# Sheet1.net
KiCad netlist of a schematic drawn in Altium Designer
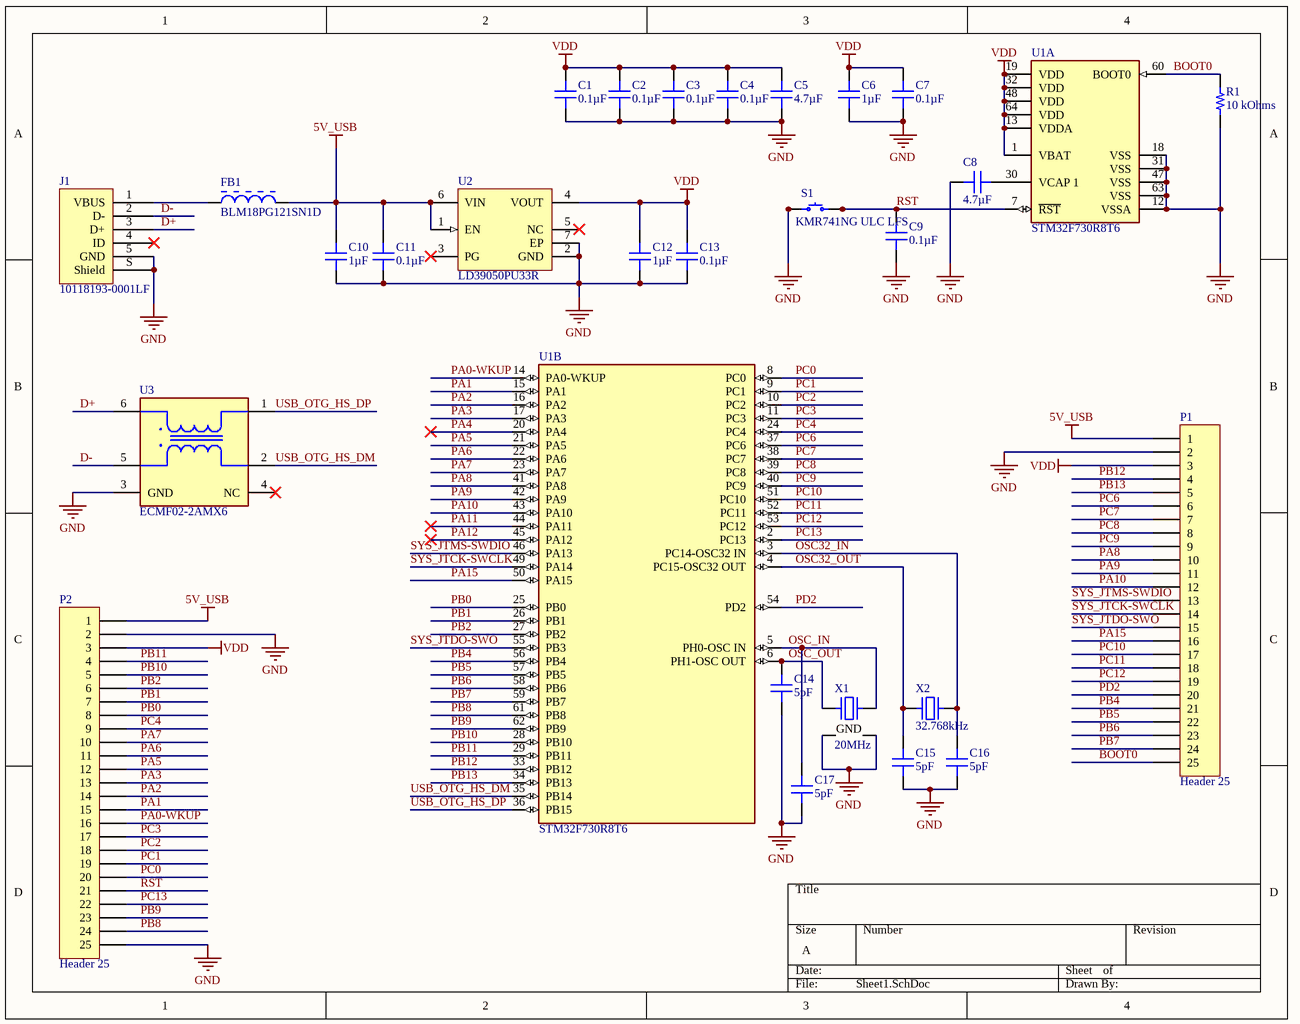
[diagram p0: Sheet1.SchDoc]

(export (version "E")
  (design (tool "Eeschema 10.0.6"))
  (components
    (comp (ref "C1")
      (value "0.1µF")
      (footprint "CAP 0603_1608")
      (description "CAP CER 0.1UF 25V X7R 0603")
      (fields (field (name "PART NUMBER") "06033C104KAZ2A") (field (name "MANUFACTURER") "AVX Corporation"))
      (libsource (lib "Celestial Altium Library - altium_library") (part "Capacitor"))
    )
    (comp (ref "C2")
      (value "0.1µF")
      (footprint "CAP 0603_1608")
      (description "CAP CER 0.1UF 25V X7R 0603")
      (fields (field (name "PART NUMBER") "06033C104KAZ2A") (field (name "MANUFACTURER") "AVX Corporation"))
      (libsource (lib "Celestial Altium Library - altium_library") (part "Capacitor"))
    )
    (comp (ref "C3")
      (value "0.1µF")
      (footprint "CAP 0603_1608")
      (description "CAP CER 0.1UF 25V X7R 0603")
      (fields (field (name "PART NUMBER") "06033C104KAZ2A") (field (name "MANUFACTURER") "AVX Corporation"))
      (libsource (lib "Celestial Altium Library - altium_library") (part "Capacitor"))
    )
    (comp (ref "C4")
      (value "0.1µF")
      (footprint "CAP 0603_1608")
      (description "CAP CER 0.1UF 25V X7R 0603")
      (fields (field (name "PART NUMBER") "06033C104KAZ2A") (field (name "MANUFACTURER") "AVX Corporation"))
      (libsource (lib "Celestial Altium Library - altium_library") (part "Capacitor"))
    )
    (comp (ref "C5")
      (value "4.7µF")
      (footprint "CAP 0603_1608")
      (description "CAP CER 4.7UF 16V X7S 0603")
      (fields
        (field (name "PART NUMBER") "GRM188C71C475KE21D")
        (field (name "MANUFACTURER") "Murata Electronics")
      )
      (libsource (lib "Celestial Altium Library - altium_library") (part "Capacitor"))
    )
    (comp (ref "C6")
      (value "1µF")
      (footprint "CAP 0603_1608")
      (description "CAP CER 1UF 25V X7R 0603")
      (fields (field (name "PART NUMBER") "06033C105KAT4A") (field (name "MANUFACTURER") "AVX Corporation"))
      (libsource (lib "Celestial Altium Library - altium_library") (part "Capacitor"))
    )
    (comp (ref "C7")
      (value "0.1µF")
      (footprint "CAP 0603_1608")
      (description "CAP CER 0.1UF 25V X7R 0603")
      (fields (field (name "PART NUMBER") "06033C104KAZ2A") (field (name "MANUFACTURER") "AVX Corporation"))
      (libsource (lib "Celestial Altium Library - altium_library") (part "Capacitor"))
    )
    (comp (ref "C8")
      (value "4.7µF")
      (footprint "CAP 0603_1608")
      (description "CAP CER 4.7UF 16V X7S 0603")
      (fields
        (field (name "PART NUMBER") "GRM188C71C475KE21D")
        (field (name "MANUFACTURER") "Murata Electronics")
      )
      (libsource (lib "Celestial Altium Library - altium_library") (part "Capacitor"))
    )
    (comp (ref "C9")
      (value "0.1µF")
      (footprint "CAP 0603_1608")
      (description "CAP CER 0.1UF 25V X7R 0603")
      (fields (field (name "PART NUMBER") "06033C104KAZ2A") (field (name "MANUFACTURER") "AVX Corporation"))
      (libsource (lib "Celestial Altium Library - altium_library") (part "Capacitor"))
    )
    (comp (ref "C10")
      (value "1µF")
      (footprint "CAP 0603_1608")
      (description "CAP CER 1UF 25V X7R 0603")
      (fields (field (name "PART NUMBER") "06033C105KAT4A") (field (name "MANUFACTURER") "AVX Corporation"))
      (libsource (lib "Celestial Altium Library - altium_library") (part "Capacitor"))
    )
    (comp (ref "C11")
      (value "0.1µF")
      (footprint "CAP 0603_1608")
      (description "CAP CER 0.1UF 25V X7R 0603")
      (fields (field (name "PART NUMBER") "06033C104KAZ2A") (field (name "MANUFACTURER") "AVX Corporation"))
      (libsource (lib "Celestial Altium Library - altium_library") (part "Capacitor"))
    )
    (comp (ref "C12")
      (value "1µF")
      (footprint "CAP 0603_1608")
      (description "CAP CER 1UF 25V X7R 0603")
      (fields (field (name "PART NUMBER") "06033C105KAT4A") (field (name "MANUFACTURER") "AVX Corporation"))
      (libsource (lib "Celestial Altium Library - altium_library") (part "Capacitor"))
    )
    (comp (ref "C13")
      (value "0.1µF")
      (footprint "CAP 0603_1608")
      (description "CAP CER 0.1UF 25V X7R 0603")
      (fields (field (name "PART NUMBER") "06033C104KAZ2A") (field (name "MANUFACTURER") "AVX Corporation"))
      (libsource (lib "Celestial Altium Library - altium_library") (part "Capacitor"))
    )
    (comp (ref "C14")
      (value "5pF")
      (footprint "CAP 0603_1608")
      (description "CAP CER 5PF 50V NP0 0603")
      (fields (field (name "PART NUMBER") "CBR06C509A5GAC") (field (name "MANUFACTURER") "KEMET"))
      (libsource (lib "Celestial Altium Library - altium_library") (part "Capacitor"))
    )
    (comp (ref "C15")
      (value "5pF")
      (footprint "CAP 0603_1608")
      (description "CAP CER 5PF 50V NP0 0603")
      (fields (field (name "PART NUMBER") "CBR06C509A5GAC") (field (name "MANUFACTURER") "KEMET"))
      (libsource (lib "Celestial Altium Library - altium_library") (part "Capacitor"))
    )
    (comp (ref "C16")
      (value "5pF")
      (footprint "CAP 0603_1608")
      (description "CAP CER 5PF 50V NP0 0603")
      (fields (field (name "PART NUMBER") "CBR06C509A5GAC") (field (name "MANUFACTURER") "KEMET"))
      (libsource (lib "Celestial Altium Library - altium_library") (part "Capacitor"))
    )
    (comp (ref "C17")
      (value "5pF")
      (footprint "CAP 0603_1608")
      (description "CAP CER 5PF 50V NP0 0603")
      (fields (field (name "PART NUMBER") "CBR06C509A5GAC") (field (name "MANUFACTURER") "KEMET"))
      (libsource (lib "Celestial Altium Library - altium_library") (part "Capacitor"))
    )
    (comp (ref "FB1")
      (value "BLM18PG121SN1D")
      (footprint "MURA-BLM18PG_KG-B25-CHIP-2_V1")
      (fields (field (name "MANUFACTURER") "Murata"))
      (libsource (lib "Altium Content Vault") (part "MURA-FB-2"))
    )
    (comp (ref "J1")
      (value "10118193-0001LF")
      (footprint "FCI USB 10118193-0001LF")
      (description "CONN RCPT USB2.0 MICRO B SMD R/A")
      (fields (field (name "MANUFACTURER") "Amphenol ICC (FCI)"))
      (libsource (lib "Celestial Altium Library - altium_library") (part "USB 2.0 Type B Micro"))
    )
    (comp (ref "P1")
      (value "Header 25")
      (footprint "HDR1X25")
      (description "Header, 25-Pin")
      (fields (field (name "PUBLISHER") "Altium Limited"))
      (libsource (lib "") (part "Header 25_1"))
    )
    (comp (ref "P2")
      (value "Header 25")
      (footprint "HDR1X25")
      (description "Header, 25-Pin")
      (fields (field (name "PUBLISHER") "Altium Limited"))
      (libsource (lib "Miscellaneous Connectors") (part "Header 25"))
    )
    (comp (ref "R1")
      (value "10 kOhms")
      (footprint "RES 0603_1608")
      (description "RES SMD 10K OHM 1% 1/4W 0603")
      (fields
        (field (name "PART NUMBER") "ERJ-PA3F1002V")
        (field (name "MANUFACTURER") "Panasonic Electronic Components")
      )
      (libsource (lib "Celestial Altium Library - altium_library") (part "Resistor"))
    )
    (comp (ref "S1")
      (value "KMR741NG ULC LFS")
      (footprint "C&K KMR7")
      (description "SWITCH TACTILE SPST-NO 50MA 32V")
      (fields (field (name "MANUFACTURER") "C&K"))
      (libsource (lib "Celestial Altium Library - altium_library") (part "SPST-NO 4 PIN"))
    )
    (comp (ref "U1")
      (value "STM32F730R8T6")
      (footprint "FP-LQFP64-5W-IPC_C")
      (fields (field (name "MANUFACTURER") "STMicroelectronics"))
      (libsource (lib "Schlib1") (part "STM32F730R8T6"))
    )
    (comp (ref "U2")
      (value "LD39050PU33R")
      (footprint "DFN6D_L")
      (description "500 mA Low Quiescent Current Low Noise Voltage Regulator, 3.3V, 6-Pin VDFDPN, Tape and Reel")
      (libsource (lib "Altium Content Vault") (part "PM-REG-LD39050-SQ7"))
    )
    (comp (ref "U3")
      (value "ECMF02-2AMX6")
      (footprint "FP-QFN-6L-MFG")
      (description "CMC 200MA 2LN SMD ESD")
      (fields
        (field (name "MANUFACTURER") "STMicroelectronics")
        (field (name "OCTOPART") "https://octopart.com/ecmf02-2amx6-stmicroelectronics-44353078")
      )
      (libsource (lib "Altium Content Vault") (part "8feffc7f24acfb857157da90e949b57"))
    )
    (comp (ref "X1")
      (value "20MHz")
      (footprint "NDK NX3225SA")
      (description "CRYSTAL 20.0000MHZ 8PF SMD")
      (fields
        (field (name "PART NUMBER") "NX3225SA-20.000M-STD-CSR-1")
        (field (name "MANUFACTURER") "NDK America, Inc.")
      )
      (libsource (lib "Celestial Altium Library - altium_library") (part "NDK Crystal NX3225SA"))
    )
    (comp (ref "X2")
      (value "32.768kHz")
      (footprint "ABRACON ABS06")
      (description "IOT 32.786KHZ XTAL")
      (fields
        (field (name "PART NUMBER") "ABS06-127-32.768KHZ-T")
        (field (name "MANUFACTURER") "Abracon LLC")
      )
      (libsource (lib "Celestial Altium Library - altium_library") (part "Abracon Crystal ABS06"))
    )
  )
  (nets
    (net (code "1") (name "/BOOT0") (class "Default")
      (node (ref "P1") (pin "25") (pinfunction "25_25") (pintype "passive"))
      (node (ref "R1") (pin "2") (pinfunction "2_2") (pintype "passive"))
      (node (ref "U1") (pin "60") (pinfunction "BOOT0_60") (pintype "input"))
    )
    (net (code "2") (name "/D+") (class "Default")
      (node (ref "J1") (pin "3") (pinfunction "D+_3") (pintype "passive"))
      (node (ref "U3") (pin "6") (pinfunction "D+_6") (pintype "passive"))
    )
    (net (code "3") (name "/D-") (class "Default")
      (node (ref "J1") (pin "2") (pinfunction "D-_2") (pintype "passive"))
      (node (ref "U3") (pin "5") (pinfunction "D-_5") (pintype "passive"))
    )
    (net (code "4") (name "/OSC32_IN") (class "Default")
      (node (ref "C16") (pin "2") (pinfunction "2_2") (pintype "passive"))
      (node (ref "U1") (pin "3") (pinfunction "PC14-OSC32_IN_3") (pintype "bidirectional"))
      (node (ref "X2") (pin "2") (pinfunction "2_2") (pintype "passive"))
    )
    (net (code "5") (name "/OSC32_OUT") (class "Default")
      (node (ref "C15") (pin "2") (pinfunction "2_2") (pintype "passive"))
      (node (ref "U1") (pin "4") (pinfunction "PC15-OSC32_OUT_4") (pintype "bidirectional"))
      (node (ref "X2") (pin "1") (pinfunction "1_1") (pintype "passive"))
    )
    (net (code "6") (name "/OSC_IN") (class "Default")
      (node (ref "C17") (pin "2") (pinfunction "2_2") (pintype "passive"))
      (node (ref "U1") (pin "5") (pinfunction "PH0-OSC_IN_5") (pintype "bidirectional"))
      (node (ref "X1") (pin "3") (pinfunction "3_3") (pintype "passive"))
    )
    (net (code "7") (name "/OSC_OUT") (class "Default")
      (node (ref "C14") (pin "2") (pinfunction "2_2") (pintype "passive"))
      (node (ref "U1") (pin "6") (pinfunction "PH1-OSC_OUT_6") (pintype "bidirectional"))
      (node (ref "X1") (pin "1") (pinfunction "1_1") (pintype "passive"))
    )
    (net (code "8") (name "/PA0-WKUP") (class "Default")
      (node (ref "P2") (pin "16") (pinfunction "16_16") (pintype "passive"))
      (node (ref "U1") (pin "14") (pinfunction "PA0-WKUP_14") (pintype "bidirectional"))
    )
    (net (code "9") (name "/PA1") (class "Default")
      (node (ref "P2") (pin "15") (pinfunction "15_15") (pintype "passive"))
      (node (ref "U1") (pin "15") (pinfunction "PA1_15") (pintype "bidirectional"))
    )
    (net (code "10") (name "/PA2") (class "Default")
      (node (ref "P2") (pin "14") (pinfunction "14_14") (pintype "passive"))
      (node (ref "U1") (pin "16") (pinfunction "PA2_16") (pintype "bidirectional"))
    )
    (net (code "11") (name "/PA3") (class "Default")
      (node (ref "P2") (pin "13") (pinfunction "13_13") (pintype "passive"))
      (node (ref "U1") (pin "17") (pinfunction "PA3_17") (pintype "bidirectional"))
    )
    (net (code "12") (name "/PA4") (class "Default")
      (node (ref "U1") (pin "20") (pinfunction "PA4_20") (pintype "bidirectional+no_connect"))
    )
    (net (code "13") (name "/PA5") (class "Default")
      (node (ref "P2") (pin "12") (pinfunction "12_12") (pintype "passive"))
      (node (ref "U1") (pin "21") (pinfunction "PA5_21") (pintype "bidirectional"))
    )
    (net (code "14") (name "/PA6") (class "Default")
      (node (ref "P2") (pin "11") (pinfunction "11_11") (pintype "passive"))
      (node (ref "U1") (pin "22") (pinfunction "PA6_22") (pintype "bidirectional"))
    )
    (net (code "15") (name "/PA7") (class "Default")
      (node (ref "P2") (pin "10") (pinfunction "10_10") (pintype "passive"))
      (node (ref "U1") (pin "23") (pinfunction "PA7_23") (pintype "bidirectional"))
    )
    (net (code "16") (name "/PA8") (class "Default")
      (node (ref "P1") (pin "10") (pinfunction "10_10") (pintype "passive"))
      (node (ref "U1") (pin "41") (pinfunction "PA8_41") (pintype "bidirectional"))
    )
    (net (code "17") (name "/PA9") (class "Default")
      (node (ref "P1") (pin "11") (pinfunction "11_11") (pintype "passive"))
      (node (ref "U1") (pin "42") (pinfunction "PA9_42") (pintype "bidirectional"))
    )
    (net (code "18") (name "/PA10") (class "Default")
      (node (ref "P1") (pin "12") (pinfunction "12_12") (pintype "passive"))
      (node (ref "U1") (pin "43") (pinfunction "PA10_43") (pintype "bidirectional"))
    )
    (net (code "19") (name "/PA11") (class "Default")
      (node (ref "U1") (pin "44") (pinfunction "PA11_44") (pintype "bidirectional+no_connect"))
    )
    (net (code "20") (name "/PA12") (class "Default")
      (node (ref "U1") (pin "45") (pinfunction "PA12_45") (pintype "bidirectional+no_connect"))
    )
    (net (code "21") (name "/PA15") (class "Default")
      (node (ref "P1") (pin "16") (pinfunction "16_16") (pintype "passive"))
      (node (ref "U1") (pin "50") (pinfunction "PA15_50") (pintype "bidirectional"))
    )
    (net (code "22") (name "/PB0") (class "Default")
      (node (ref "P2") (pin "8") (pinfunction "8_8") (pintype "passive"))
      (node (ref "U1") (pin "25") (pinfunction "PB0_25") (pintype "bidirectional"))
    )
    (net (code "23") (name "/PB1") (class "Default")
      (node (ref "P2") (pin "7") (pinfunction "7_7") (pintype "passive"))
      (node (ref "U1") (pin "26") (pinfunction "PB1_26") (pintype "bidirectional"))
    )
    (net (code "24") (name "/PB2") (class "Default")
      (node (ref "P2") (pin "6") (pinfunction "6_6") (pintype "passive"))
      (node (ref "U1") (pin "27") (pinfunction "PB2_27") (pintype "bidirectional"))
    )
    (net (code "25") (name "/PB4") (class "Default")
      (node (ref "P1") (pin "21") (pinfunction "21_21") (pintype "passive"))
      (node (ref "U1") (pin "56") (pinfunction "PB4_56") (pintype "bidirectional"))
    )
    (net (code "26") (name "/PB5") (class "Default")
      (node (ref "P1") (pin "22") (pinfunction "22_22") (pintype "passive"))
      (node (ref "U1") (pin "57") (pinfunction "PB5_57") (pintype "bidirectional"))
    )
    (net (code "27") (name "/PB6") (class "Default")
      (node (ref "P1") (pin "23") (pinfunction "23_23") (pintype "passive"))
      (node (ref "U1") (pin "58") (pinfunction "PB6_58") (pintype "bidirectional"))
    )
    (net (code "28") (name "/PB7") (class "Default")
      (node (ref "P1") (pin "24") (pinfunction "24_24") (pintype "passive"))
      (node (ref "U1") (pin "59") (pinfunction "PB7_59") (pintype "bidirectional"))
    )
    (net (code "29") (name "/PB8") (class "Default")
      (node (ref "P2") (pin "24") (pinfunction "24_24") (pintype "passive"))
      (node (ref "U1") (pin "61") (pinfunction "PB8_61") (pintype "bidirectional"))
    )
    (net (code "30") (name "/PB9") (class "Default")
      (node (ref "P2") (pin "23") (pinfunction "23_23") (pintype "passive"))
      (node (ref "U1") (pin "62") (pinfunction "PB9_62") (pintype "bidirectional"))
    )
    (net (code "31") (name "/PB10") (class "Default")
      (node (ref "P2") (pin "5") (pinfunction "5_5") (pintype "passive"))
      (node (ref "U1") (pin "28") (pinfunction "PB10_28") (pintype "bidirectional"))
    )
    (net (code "32") (name "/PB11") (class "Default")
      (node (ref "P2") (pin "4") (pinfunction "4_4") (pintype "passive"))
      (node (ref "U1") (pin "29") (pinfunction "PB11_29") (pintype "bidirectional"))
    )
    (net (code "33") (name "/PB12") (class "Default")
      (node (ref "P1") (pin "4") (pinfunction "4_4") (pintype "passive"))
      (node (ref "U1") (pin "33") (pinfunction "PB12_33") (pintype "bidirectional"))
    )
    (net (code "34") (name "/PB13") (class "Default")
      (node (ref "P1") (pin "5") (pinfunction "5_5") (pintype "passive"))
      (node (ref "U1") (pin "34") (pinfunction "PB13_34") (pintype "bidirectional"))
    )
    (net (code "35") (name "/PC0") (class "Default")
      (node (ref "P2") (pin "20") (pinfunction "20_20") (pintype "passive"))
      (node (ref "U1") (pin "8") (pinfunction "PC0_8") (pintype "bidirectional"))
    )
    (net (code "36") (name "/PC1") (class "Default")
      (node (ref "P2") (pin "19") (pinfunction "19_19") (pintype "passive"))
      (node (ref "U1") (pin "9") (pinfunction "PC1_9") (pintype "bidirectional"))
    )
    (net (code "37") (name "/PC2") (class "Default")
      (node (ref "P2") (pin "18") (pinfunction "18_18") (pintype "passive"))
      (node (ref "U1") (pin "10") (pinfunction "PC2_10") (pintype "bidirectional"))
    )
    (net (code "38") (name "/PC3") (class "Default")
      (node (ref "P2") (pin "17") (pinfunction "17_17") (pintype "passive"))
      (node (ref "U1") (pin "11") (pinfunction "PC3_11") (pintype "bidirectional"))
    )
    (net (code "39") (name "/PC4") (class "Default")
      (node (ref "P2") (pin "9") (pinfunction "9_9") (pintype "passive"))
      (node (ref "U1") (pin "24") (pinfunction "PC4_24") (pintype "bidirectional"))
    )
    (net (code "40") (name "/PC6") (class "Default")
      (node (ref "P1") (pin "6") (pinfunction "6_6") (pintype "passive"))
      (node (ref "U1") (pin "37") (pinfunction "PC6_37") (pintype "bidirectional"))
    )
    (net (code "41") (name "/PC7") (class "Default")
      (node (ref "P1") (pin "7") (pinfunction "7_7") (pintype "passive"))
      (node (ref "U1") (pin "38") (pinfunction "PC7_38") (pintype "bidirectional"))
    )
    (net (code "42") (name "/PC8") (class "Default")
      (node (ref "P1") (pin "8") (pinfunction "8_8") (pintype "passive"))
      (node (ref "U1") (pin "39") (pinfunction "PC8_39") (pintype "bidirectional"))
    )
    (net (code "43") (name "/PC9") (class "Default")
      (node (ref "P1") (pin "9") (pinfunction "9_9") (pintype "passive"))
      (node (ref "U1") (pin "40") (pinfunction "PC9_40") (pintype "bidirectional"))
    )
    (net (code "44") (name "/PC10") (class "Default")
      (node (ref "P1") (pin "17") (pinfunction "17_17") (pintype "passive"))
      (node (ref "U1") (pin "51") (pinfunction "PC10_51") (pintype "bidirectional"))
    )
    (net (code "45") (name "/PC11") (class "Default")
      (node (ref "P1") (pin "18") (pinfunction "18_18") (pintype "passive"))
      (node (ref "U1") (pin "52") (pinfunction "PC11_52") (pintype "bidirectional"))
    )
    (net (code "46") (name "/PC12") (class "Default")
      (node (ref "P1") (pin "19") (pinfunction "19_19") (pintype "passive"))
      (node (ref "U1") (pin "53") (pinfunction "PC12_53") (pintype "bidirectional"))
    )
    (net (code "47") (name "/PC13") (class "Default")
      (node (ref "P2") (pin "22") (pinfunction "22_22") (pintype "passive"))
      (node (ref "U1") (pin "2") (pinfunction "PC13_2") (pintype "bidirectional"))
    )
    (net (code "48") (name "/PD2") (class "Default")
      (node (ref "P1") (pin "20") (pinfunction "20_20") (pintype "passive"))
      (node (ref "U1") (pin "54") (pinfunction "PD2_54") (pintype "bidirectional"))
    )
    (net (code "49") (name "/RST") (class "Default")
      (node (ref "C9") (pin "1") (pinfunction "1_1") (pintype "passive"))
      (node (ref "P2") (pin "21") (pinfunction "21_21") (pintype "passive"))
      (node (ref "S1") (pin "3") (pinfunction "3_3") (pintype "passive"))
      (node (ref "S1") (pin "4") (pinfunction "4_4") (pintype "passive"))
      (node (ref "U1") (pin "7") (pinfunction "~{RST}_7") (pintype "bidirectional"))
    )
    (net (code "50") (name "/SYS_JTCK-SWCLK") (class "Default")
      (node (ref "P1") (pin "14") (pinfunction "14_14") (pintype "passive"))
      (node (ref "U1") (pin "49") (pinfunction "PA14_49") (pintype "bidirectional"))
    )
    (net (code "51") (name "/SYS_JTDO-SWO") (class "Default")
      (node (ref "P1") (pin "15") (pinfunction "15_15") (pintype "passive"))
      (node (ref "U1") (pin "55") (pinfunction "PB3_55") (pintype "bidirectional"))
    )
    (net (code "52") (name "/SYS_JTMS-SWDIO") (class "Default")
      (node (ref "P1") (pin "13") (pinfunction "13_13") (pintype "passive"))
      (node (ref "U1") (pin "46") (pinfunction "PA13_46") (pintype "bidirectional"))
    )
    (net (code "53") (name "/USB_OTG_HS_DM") (class "Default")
      (node (ref "U1") (pin "35") (pinfunction "PB14_35") (pintype "bidirectional"))
      (node (ref "U3") (pin "2") (pinfunction "D-_2") (pintype "passive"))
    )
    (net (code "54") (name "/USB_OTG_HS_DP") (class "Default")
      (node (ref "U1") (pin "36") (pinfunction "PB15_36") (pintype "bidirectional"))
      (node (ref "U3") (pin "1") (pinfunction "D+_1") (pintype "passive"))
    )
    (net (code "55") (name "5V_USB") (class "Default")
      (node (ref "C10") (pin "2") (pinfunction "2_2") (pintype "passive"))
      (node (ref "C11") (pin "2") (pinfunction "2_2") (pintype "passive"))
      (node (ref "FB1") (pin "2") (pinfunction "2_2") (pintype "passive"))
      (node (ref "P1") (pin "1") (pinfunction "1_1") (pintype "passive"))
      (node (ref "P2") (pin "1") (pinfunction "1_1") (pintype "passive"))
      (node (ref "U2") (pin "1") (pinfunction "EN_1") (pintype "input"))
      (node (ref "U2") (pin "6") (pinfunction "VIN_6") (pintype "power_in"))
    )
    (net (code "56") (name "GND") (class "Default")
      (node (ref "C1") (pin "1") (pinfunction "1_1") (pintype "passive"))
      (node (ref "C10") (pin "1") (pinfunction "1_1") (pintype "passive"))
      (node (ref "C11") (pin "1") (pinfunction "1_1") (pintype "passive"))
      (node (ref "C12") (pin "1") (pinfunction "1_1") (pintype "passive"))
      (node (ref "C13") (pin "2") (pinfunction "2_2") (pintype "passive"))
      (node (ref "C14") (pin "1") (pinfunction "1_1") (pintype "passive"))
      (node (ref "C15") (pin "1") (pinfunction "1_1") (pintype "passive"))
      (node (ref "C16") (pin "1") (pinfunction "1_1") (pintype "passive"))
      (node (ref "C17") (pin "1") (pinfunction "1_1") (pintype "passive"))
      (node (ref "C2") (pin "1") (pinfunction "1_1") (pintype "passive"))
      (node (ref "C3") (pin "1") (pinfunction "1_1") (pintype "passive"))
      (node (ref "C4") (pin "1") (pinfunction "1_1") (pintype "passive"))
      (node (ref "C5") (pin "1") (pinfunction "1_1") (pintype "passive"))
      (node (ref "C6") (pin "2") (pinfunction "2_2") (pintype "passive"))
      (node (ref "C7") (pin "2") (pinfunction "2_2") (pintype "passive"))
      (node (ref "C8") (pin "2") (pinfunction "2_2") (pintype "passive"))
      (node (ref "C9") (pin "2") (pinfunction "2_2") (pintype "passive"))
      (node (ref "J1") (pin "5") (pinfunction "GND_5") (pintype "passive"))
      (node (ref "J1") (pin "S") (pinfunction "Shield_S") (pintype "passive"))
      (node (ref "P1") (pin "2") (pinfunction "2_2") (pintype "passive"))
      (node (ref "P2") (pin "2") (pinfunction "2_2") (pintype "passive"))
      (node (ref "P2") (pin "25") (pinfunction "25_25") (pintype "passive"))
      (node (ref "R1") (pin "1") (pinfunction "1_1") (pintype "passive"))
      (node (ref "S1") (pin "1") (pinfunction "1_1") (pintype "passive"))
      (node (ref "S1") (pin "2") (pinfunction "2_2") (pintype "passive"))
      (node (ref "U1") (pin "12") (pinfunction "VSSA_12") (pintype "power_in"))
      (node (ref "U1") (pin "18") (pinfunction "VSS_18") (pintype "power_in"))
      (node (ref "U1") (pin "31") (pinfunction "VSS_31") (pintype "power_in"))
      (node (ref "U1") (pin "47") (pinfunction "VSS_47") (pintype "power_in"))
      (node (ref "U1") (pin "63") (pinfunction "VSS_63") (pintype "power_in"))
      (node (ref "U2") (pin "2") (pinfunction "GND_2") (pintype "power_in"))
      (node (ref "U2") (pin "7") (pinfunction "EP_7") (pintype "power_in"))
      (node (ref "U3") (pin "3") (pinfunction "GND_3") (pintype "power_in"))
      (node (ref "X1") (pin "2") (pinfunction "GND_2") (pintype "passive"))
      (node (ref "X1") (pin "4") (pinfunction "GND_4") (pintype "passive"))
    )
    (net (code "57") (name "Net-(J1-VBUS)") (class "Default")
      (node (ref "FB1") (pin "1") (pinfunction "1_1") (pintype "passive"))
      (node (ref "J1") (pin "1") (pinfunction "VBUS_1") (pintype "passive"))
    )
    (net (code "58") (name "Net-(U1A-VCAP_1)") (class "Default")
      (node (ref "C8") (pin "1") (pinfunction "1_1") (pintype "passive"))
      (node (ref "U1") (pin "30") (pinfunction "VCAP_1_30") (pintype "power_in"))
    )
    (net (code "59") (name "VDD") (class "Default")
      (node (ref "C1") (pin "2") (pinfunction "2_2") (pintype "passive"))
      (node (ref "C12") (pin "2") (pinfunction "2_2") (pintype "passive"))
      (node (ref "C13") (pin "1") (pinfunction "1_1") (pintype "passive"))
      (node (ref "C2") (pin "2") (pinfunction "2_2") (pintype "passive"))
      (node (ref "C3") (pin "2") (pinfunction "2_2") (pintype "passive"))
      (node (ref "C4") (pin "2") (pinfunction "2_2") (pintype "passive"))
      (node (ref "C5") (pin "2") (pinfunction "2_2") (pintype "passive"))
      (node (ref "C6") (pin "1") (pinfunction "1_1") (pintype "passive"))
      (node (ref "C7") (pin "1") (pinfunction "1_1") (pintype "passive"))
      (node (ref "P1") (pin "3") (pinfunction "3_3") (pintype "passive"))
      (node (ref "P2") (pin "3") (pinfunction "3_3") (pintype "passive"))
      (node (ref "U1") (pin "1") (pinfunction "VBAT_1") (pintype "power_in"))
      (node (ref "U1") (pin "13") (pinfunction "VDDA_13") (pintype "power_in"))
      (node (ref "U1") (pin "19") (pinfunction "VDD_19") (pintype "power_in"))
      (node (ref "U1") (pin "32") (pinfunction "VDD_32") (pintype "power_in"))
      (node (ref "U1") (pin "48") (pinfunction "VDD_48") (pintype "power_in"))
      (node (ref "U1") (pin "64") (pinfunction "VDD_64") (pintype "power_in"))
      (node (ref "U2") (pin "4") (pinfunction "VOUT_4") (pintype "power_in"))
    )
    (net (code "60") (name "unconnected-(J1-ID-Pad4)") (class "Default")
      (node (ref "J1") (pin "4") (pinfunction "ID_4") (pintype "passive+no_connect"))
    )
    (net (code "61") (name "unconnected-(U2-NC-Pad5)") (class "Default")
      (node (ref "U2") (pin "5") (pinfunction "NC_5") (pintype "passive+no_connect"))
    )
    (net (code "62") (name "unconnected-(U2-PG-Pad3)") (class "Default")
      (node (ref "U2") (pin "3") (pinfunction "PG_3") (pintype "open_collector+no_connect"))
    )
    (net (code "63") (name "unconnected-(U3-NC-Pad4)") (class "Default")
      (node (ref "U3") (pin "4") (pinfunction "NC_4") (pintype "passive+no_connect"))
    )
  )
)
